# USB-HUB.net
KiCad netlist of a schematic drawn in Altium Designer
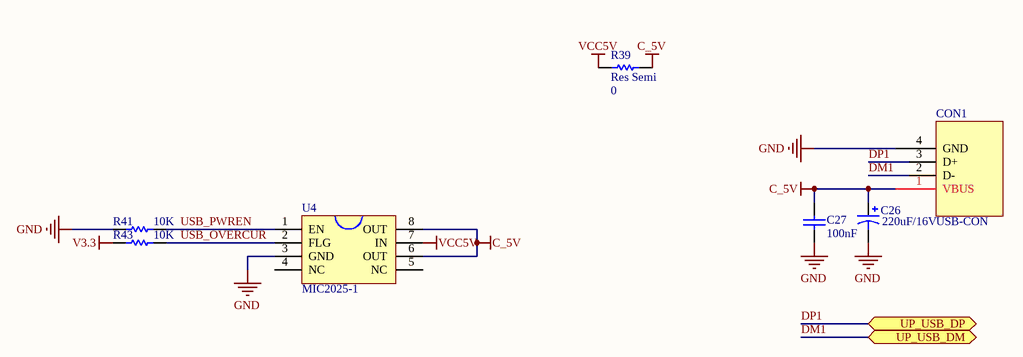
[diagram p0: USB-HUB.SchDoc]

(export (version "E")
  (design (tool "Eeschema 10.0.6"))
  (components
    (comp (ref "C26")
      (value "220uF/16V")
      (footprint "16V220U-tie")
      (description "Polarized Capacitor (Radial)")
      (fields (field (name "PUBLISHER") "Altium Limited"))
      (libsource (lib "Miscellaneous Devices") (part "Cap Pol1"))
    )
    (comp (ref "C27") (value "100nF") (footprint "R0603N") (libsource (lib "CAP") (part "CAP")))
    (comp (ref "CON1") (value "USB-CON") (footprint "1364372") (libsource (lib "Interface") (part "USB-CON")))
    (comp (ref "R39")
      (value "Res Semi")
      (footprint "6-0805_N")
      (description "Semiconductor Resistor")
      (fields (field (name "ALTIUM_VALUE") "0") (field (name "PUBLISHER") "Altium Limited"))
      (libsource (lib "Miscellaneous Devices") (part "Res Semi"))
    )
    (comp (ref "R41") (value "10K") (footprint "R0603N") (libsource (lib "RES") (part "RES")))
    (comp (ref "R43") (value "10K") (footprint "R0603N") (libsource (lib "RES") (part "RES")))
    (comp (ref "U4")
      (value "MIC2025-1")
      (footprint "SO8_N")
      (libsource (lib "Power_Charge") (part "MIC2025-1"))
    )
  )
  (nets
    (net (code "1") (name "/DM1") (class "Default")
      (node (ref "CON1") (pin "2") (pinfunction "D-_2") (pintype "passive"))
    )
    (net (code "2") (name "/DP1") (class "Default")
      (node (ref "CON1") (pin "3") (pinfunction "D+_3") (pintype "passive"))
    )
    (net (code "3") (name "/USB_OVERCUR") (class "Default")
      (node (ref "R43") (pin "1") (pinfunction "1_1") (pintype "passive"))
      (node (ref "U4") (pin "2") (pinfunction "FLG_2") (pintype "passive"))
    )
    (net (code "4") (name "/USB_PWREN") (class "Default")
      (node (ref "R41") (pin "1") (pinfunction "1_1") (pintype "passive"))
      (node (ref "U4") (pin "1") (pinfunction "EN_1") (pintype "passive"))
    )
    (net (code "5") (name "C_5V") (class "Default")
      (node (ref "C26") (pin "1") (pinfunction "1_1") (pintype "passive"))
      (node (ref "C27") (pin "2") (pinfunction "2_2") (pintype "passive"))
      (node (ref "CON1") (pin "1") (pinfunction "VBUS_1") (pintype "passive"))
      (node (ref "R39") (pin "2") (pinfunction "2_2") (pintype "passive"))
      (node (ref "U4") (pin "6") (pinfunction "OUT_6") (pintype "passive"))
      (node (ref "U4") (pin "8") (pinfunction "OUT_8") (pintype "passive"))
    )
    (net (code "6") (name "GND") (class "Default")
      (node (ref "C26") (pin "2") (pinfunction "2_2") (pintype "passive"))
      (node (ref "C27") (pin "1") (pinfunction "1_1") (pintype "passive"))
      (node (ref "CON1") (pin "4") (pinfunction "GND_4") (pintype "passive"))
      (node (ref "R41") (pin "2") (pinfunction "2_2") (pintype "passive"))
      (node (ref "U4") (pin "3") (pinfunction "GND_3") (pintype "passive"))
    )
    (net (code "7") (name "V3.3") (class "Default")
      (node (ref "R43") (pin "2") (pinfunction "2_2") (pintype "passive"))
    )
    (net (code "8") (name "VCC5V") (class "Default")
      (node (ref "R39") (pin "1") (pinfunction "1_1") (pintype "passive"))
      (node (ref "U4") (pin "7") (pinfunction "IN_7") (pintype "passive"))
    )
    (net (code "9") (name "unconnected-(U4-NC-Pad4)") (class "Default")
      (node (ref "U4") (pin "4") (pinfunction "NC_4") (pintype "passive"))
    )
    (net (code "10") (name "unconnected-(U4-NC-Pad5)") (class "Default")
      (node (ref "U4") (pin "5") (pinfunction "NC_5") (pintype "passive"))
    )
  )
)
